# indicator_lights.net
KiCad netlist of a schematic drawn in EAGLE
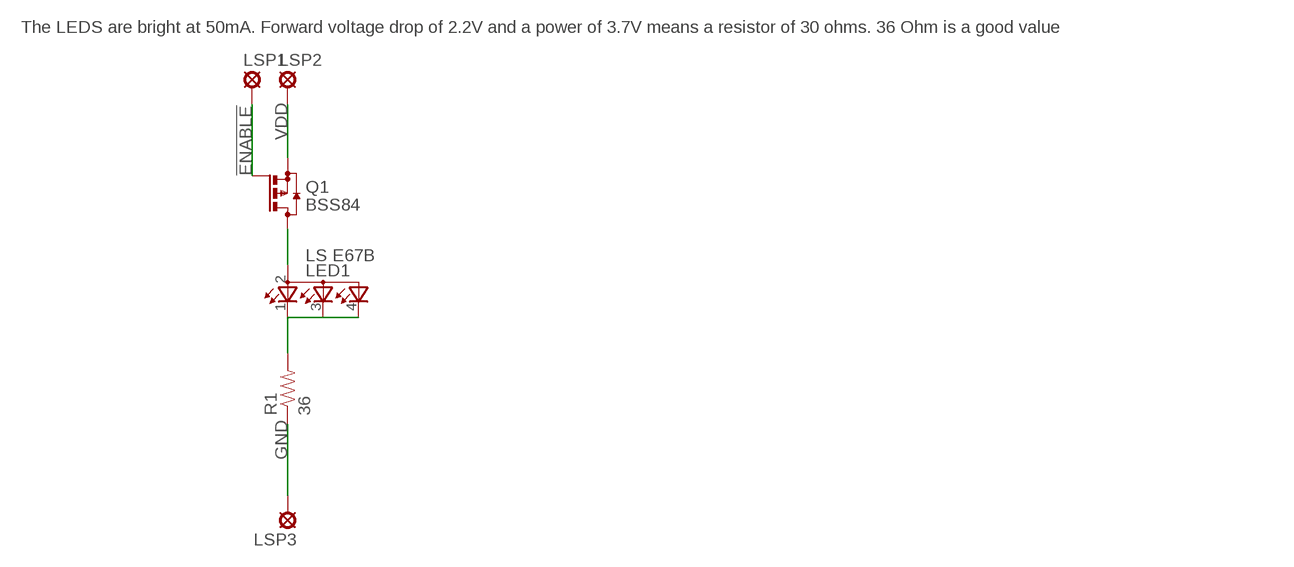
[diagram p0: schematic, sheet 1]

(export (version "E")
  (design (tool "Eeschema 10.0.6"))
  (components
    (comp (ref "LED1")
      (value "LS E67B")
      (footprint "eagle-import:P-LCC-4-3")
      (libsource (lib "eagle-import") (part "TOPLED-3"))
    )
    (comp (ref "LSP1")
      (value "MCS10B")
      (footprint "eagle-import:MCS10B")
      (libsource (lib "eagle-import") (part "MCS10B"))
    )
    (comp (ref "LSP2")
      (value "MCS10B")
      (footprint "eagle-import:MCS10B")
      (libsource (lib "eagle-import") (part "MCS10B"))
    )
    (comp (ref "LSP3")
      (value "MCS10B")
      (footprint "eagle-import:MCS10B")
      (libsource (lib "eagle-import") (part "MCS10B"))
    )
    (comp (ref "Q1")
      (value "BSS84")
      (footprint "eagle-import:SOT23")
      (libsource (lib "eagle-import") (part "BSS84"))
    )
    (comp (ref "R1")
      (value "36")
      (footprint "eagle-import:0603-RES")
      (libsource (lib "eagle-import") (part "RESISTOR0603-RES"))
    )
  )
  (nets
    (net (code "1") (name "/GND") (class "Default")
      (node (ref "LSP3") (pin "MP") (pinfunction "MP_MP") (pintype "passive"))
      (node (ref "R1") (pin "1") (pinfunction "1_1") (pintype "passive"))
    )
    (net (code "2") (name "/VDD") (class "Default")
      (node (ref "LSP2") (pin "MP") (pinfunction "MP_MP") (pintype "passive"))
      (node (ref "Q1") (pin "2") (pinfunction "S_2") (pintype "passive"))
    )
    (net (code "3") (name "/~{ENABLE}") (class "Default")
      (node (ref "LSP1") (pin "MP") (pinfunction "MP_MP") (pintype "passive"))
      (node (ref "Q1") (pin "1") (pinfunction "G_1") (pintype "passive"))
    )
    (net (code "4") (name "Net-(LED1-A2)") (class "Default")
      (node (ref "LED1") (pin "2") (pinfunction "A2_2") (pintype "passive"))
      (node (ref "Q1") (pin "3") (pinfunction "D_3") (pintype "passive"))
    )
    (net (code "5") (name "Net-(LED1-CBLUE)") (class "Default")
      (node (ref "LED1") (pin "1") (pinfunction "CRED_1") (pintype "passive"))
      (node (ref "LED1") (pin "3") (pinfunction "CBLUE_3") (pintype "passive"))
      (node (ref "LED1") (pin "4") (pinfunction "CGREEN_4") (pintype "passive"))
      (node (ref "R1") (pin "2") (pinfunction "2_2") (pintype "passive"))
    )
  )
)
